# T_CAN.net
KiCad netlist of a schematic drawn in Altium Designer
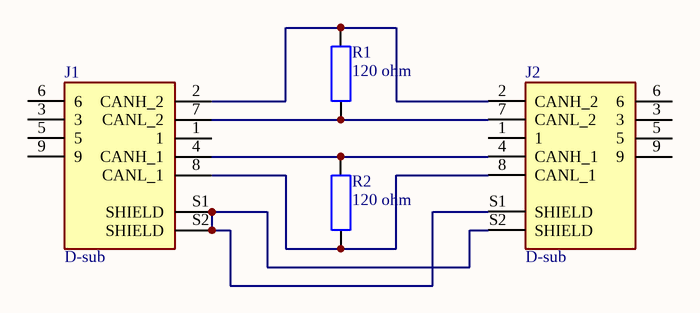
[diagram p0: T_CAN.SchDoc]

(export (version "E")
  (design (tool "Eeschema 10.0.6"))
  (components
    (comp (ref "J1")
      (value "D-sub")
      (footprint "ASSMANN_A-DF_09_A_KG-T2S")
      (description "9 Position D-Sub Receptacle, Female Sockets Connector")
      (fields (field (name "MF") "Assmann WSW") (field (name "MP") "A-DF 09 A/KG-T2S"))
      (libsource (lib "T_CAN_Schlib1") (part "A-DF_09_A_KG-T2S"))
    )
    (comp (ref "J2")
      (value "D-sub")
      (footprint "ASSMANN_A-DF_09_A_KG-T2S")
      (description "9 Position D-Sub Receptacle, Female Sockets Connector")
      (fields (field (name "MF") "Assmann WSW") (field (name "MP") "A-DF 09 A/KG-T2S"))
      (libsource (lib "") (part "A-DF_09_A_KG-T2S_1"))
    )
    (comp (ref "R1")
      (value "120 ohm")
      (footprint "R0805")
      (description "Chip Resistor Automotive Grade Thick Film 0805 120Ohm 1% Paper T/R")
      (fields
        (field (name "MANUFACTURER") "Yageo")
        (field (name "MANUFACTURER PART NUMBER") "AC0805FR-7W120RL")
      )
      (libsource (lib "T_CAN_Schlib1") (part "AC0805FR-7W120RL"))
    )
    (comp (ref "R2")
      (value "120 ohm")
      (footprint "R0805")
      (description "Chip Resistor Automotive Grade Thick Film 0805 120Ohm 1% Paper T/R")
      (fields
        (field (name "MANUFACTURER") "Yageo")
        (field (name "MANUFACTURER PART NUMBER") "AC0805FR-7W120RL")
      )
      (libsource (lib "T_CAN_Schlib1") (part "AC0805FR-7W120RL"))
    )
  )
  (nets
    (net (code "1") (name "Net-(J1-CANH_1)") (class "Default")
      (node (ref "J1") (pin "4") (pinfunction "CANH_1_4") (pintype "passive"))
      (node (ref "J2") (pin "4") (pinfunction "CANH_1_4") (pintype "passive"))
      (node (ref "R2") (pin "2") (pinfunction "2_2") (pintype "passive"))
    )
    (net (code "2") (name "Net-(J1-CANH_2)") (class "Default")
      (node (ref "J1") (pin "2") (pinfunction "CANH_2_2") (pintype "passive"))
      (node (ref "J2") (pin "2") (pinfunction "CANH_2_2") (pintype "passive"))
      (node (ref "R1") (pin "2") (pinfunction "2_2") (pintype "passive"))
    )
    (net (code "3") (name "Net-(J1-CANL_1)") (class "Default")
      (node (ref "J1") (pin "8") (pinfunction "CANL_1_8") (pintype "passive"))
      (node (ref "J2") (pin "8") (pinfunction "CANL_1_8") (pintype "passive"))
      (node (ref "R2") (pin "1") (pinfunction "1_1") (pintype "passive"))
    )
    (net (code "4") (name "Net-(J1-CANL_2)") (class "Default")
      (node (ref "J1") (pin "7") (pinfunction "CANL_2_7") (pintype "passive"))
      (node (ref "J2") (pin "7") (pinfunction "CANL_2_7") (pintype "passive"))
      (node (ref "R1") (pin "1") (pinfunction "1_1") (pintype "passive"))
    )
    (net (code "5") (name "Net-(J1-SHIELD-PadS1)") (class "Default")
      (node (ref "J1") (pin "S1") (pinfunction "SHIELD_S1") (pintype "passive"))
      (node (ref "J1") (pin "S2") (pinfunction "SHIELD_S2") (pintype "passive"))
      (node (ref "J2") (pin "S1") (pinfunction "SHIELD_S1") (pintype "passive"))
      (node (ref "J2") (pin "S2") (pinfunction "SHIELD_S2") (pintype "passive"))
    )
    (net (code "6") (name "unconnected-(J1-Pad1)") (class "Default")
      (node (ref "J1") (pin "1") (pinfunction "1_1") (pintype "passive"))
    )
    (net (code "7") (name "unconnected-(J1-Pad3)") (class "Default")
      (node (ref "J1") (pin "3") (pinfunction "3_3") (pintype "passive"))
    )
    (net (code "8") (name "unconnected-(J1-Pad5)") (class "Default")
      (node (ref "J1") (pin "5") (pinfunction "5_5") (pintype "passive"))
    )
    (net (code "9") (name "unconnected-(J1-Pad6)") (class "Default")
      (node (ref "J1") (pin "6") (pinfunction "6_6") (pintype "passive"))
    )
    (net (code "10") (name "unconnected-(J1-Pad9)") (class "Default")
      (node (ref "J1") (pin "9") (pinfunction "9_9") (pintype "passive"))
    )
    (net (code "11") (name "unconnected-(J2-Pad1)") (class "Default")
      (node (ref "J2") (pin "1") (pinfunction "1_1") (pintype "passive"))
    )
    (net (code "12") (name "unconnected-(J2-Pad3)") (class "Default")
      (node (ref "J2") (pin "3") (pinfunction "3_3") (pintype "passive"))
    )
    (net (code "13") (name "unconnected-(J2-Pad5)") (class "Default")
      (node (ref "J2") (pin "5") (pinfunction "5_5") (pintype "passive"))
    )
    (net (code "14") (name "unconnected-(J2-Pad6)") (class "Default")
      (node (ref "J2") (pin "6") (pinfunction "6_6") (pintype "passive"))
    )
    (net (code "15") (name "unconnected-(J2-Pad9)") (class "Default")
      (node (ref "J2") (pin "9") (pinfunction "9_9") (pintype "passive"))
    )
  )
)
